# vib_pot_LED2.net
KiCad netlist of a schematic drawn in EAGLE
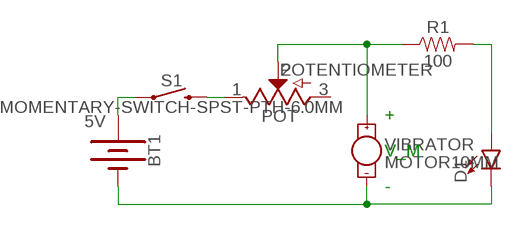
[diagram p0: schematic, sheet 1]

(export (version "E")
  (design (tool "Eeschema 10.0.6"))
  (components
    (comp (ref "BT1")
      (value "BATTERY-9V")
      (footprint "eagle-import:BATTCON_9V")
      (libsource (lib "eagle-import") (part "BATTERY-9V"))
    )
    (comp (ref "D1")
      (value "LED5MM")
      (footprint "eagle-import:LED_5MM")
      (libsource (lib "eagle-import") (part "LED5MM"))
    )
    (comp (ref "POTENTIOMETER")
      (value "POTENTIOMETER-PTH-9MM-1/20W-20%")
      (footprint "eagle-import:POT-PTH-ALPS")
      (libsource (lib "eagle-import") (part "POTENTIOMETER-PTH-9MM-1/20W-20%"))
    )
    (comp (ref "R1")
      (value "100")
      (footprint "eagle-import:AXIAL-0.3")
      (libsource (lib "eagle-import") (part "100OHM-HORIZ-1/4W-1%"))
    )
    (comp (ref "S1")
      (value "MOMENTARY-SWITCH-SPST-PTH-6.0MM")
      (footprint "eagle-import:TACTILE_SWITCH_PTH_6.0MM")
      (libsource (lib "eagle-import") (part "MOMENTARY-SWITCH-SPST-PTH-6.0MM"))
    )
    (comp (ref "VIBRATOR")
      (value "MOTOR10MM")
      (footprint "eagle-import:VIBE-MOTOR-10MM")
      (libsource (lib "eagle-import") (part "MOTOR10MM"))
    )
  )
  (nets
    (net (code "1") (name "Net-(BT1-Pad+)") (class "Default")
      (node (ref "BT1") (pin "+") (pinfunction "+_+") (pintype "power_in"))
      (node (ref "S1") (pin "1") (pinfunction "1_1") (pintype "passive"))
    )
    (net (code "2") (name "Net-(D1-C)") (class "Default")
      (node (ref "BT1") (pin "-") (pinfunction "-_-") (pintype "power_in"))
      (node (ref "D1") (pin "K") (pinfunction "C_K") (pintype "passive"))
      (node (ref "VIBRATOR") (pin "-") (pinfunction "-_-") (pintype "bidirectional"))
    )
    (net (code "3") (name "Net-(POTENTIOMETER-E)") (class "Default")
      (node (ref "POTENTIOMETER") (pin "P$1") (pinfunction "E_P$1") (pintype "passive"))
      (node (ref "S1") (pin "3") (pinfunction "2_3") (pintype "passive"))
    )
    (net (code "4") (name "Net-(POTENTIOMETER-S)") (class "Default")
      (node (ref "POTENTIOMETER") (pin "P$2") (pinfunction "S_P$2") (pintype "passive"))
      (node (ref "R1") (pin "P$1") (pinfunction "1_P$1") (pintype "passive"))
      (node (ref "VIBRATOR") (pin "+") (pinfunction "+_+") (pintype "bidirectional"))
    )
    (net (code "5") (name "Net-(R1-2)") (class "Default")
      (node (ref "D1") (pin "A") (pinfunction "A_A") (pintype "passive"))
      (node (ref "R1") (pin "P$2") (pinfunction "2_P$2") (pintype "passive"))
    )
    (net (code "6") (name "unconnected-(POTENTIOMETER-A-PadP$3)") (class "Default")
      (node (ref "POTENTIOMETER") (pin "P$3") (pinfunction "A_P$3") (pintype "passive"))
    )
  )
)
